# Sheet4.net
KiCad netlist of a schematic drawn in Altium Designer
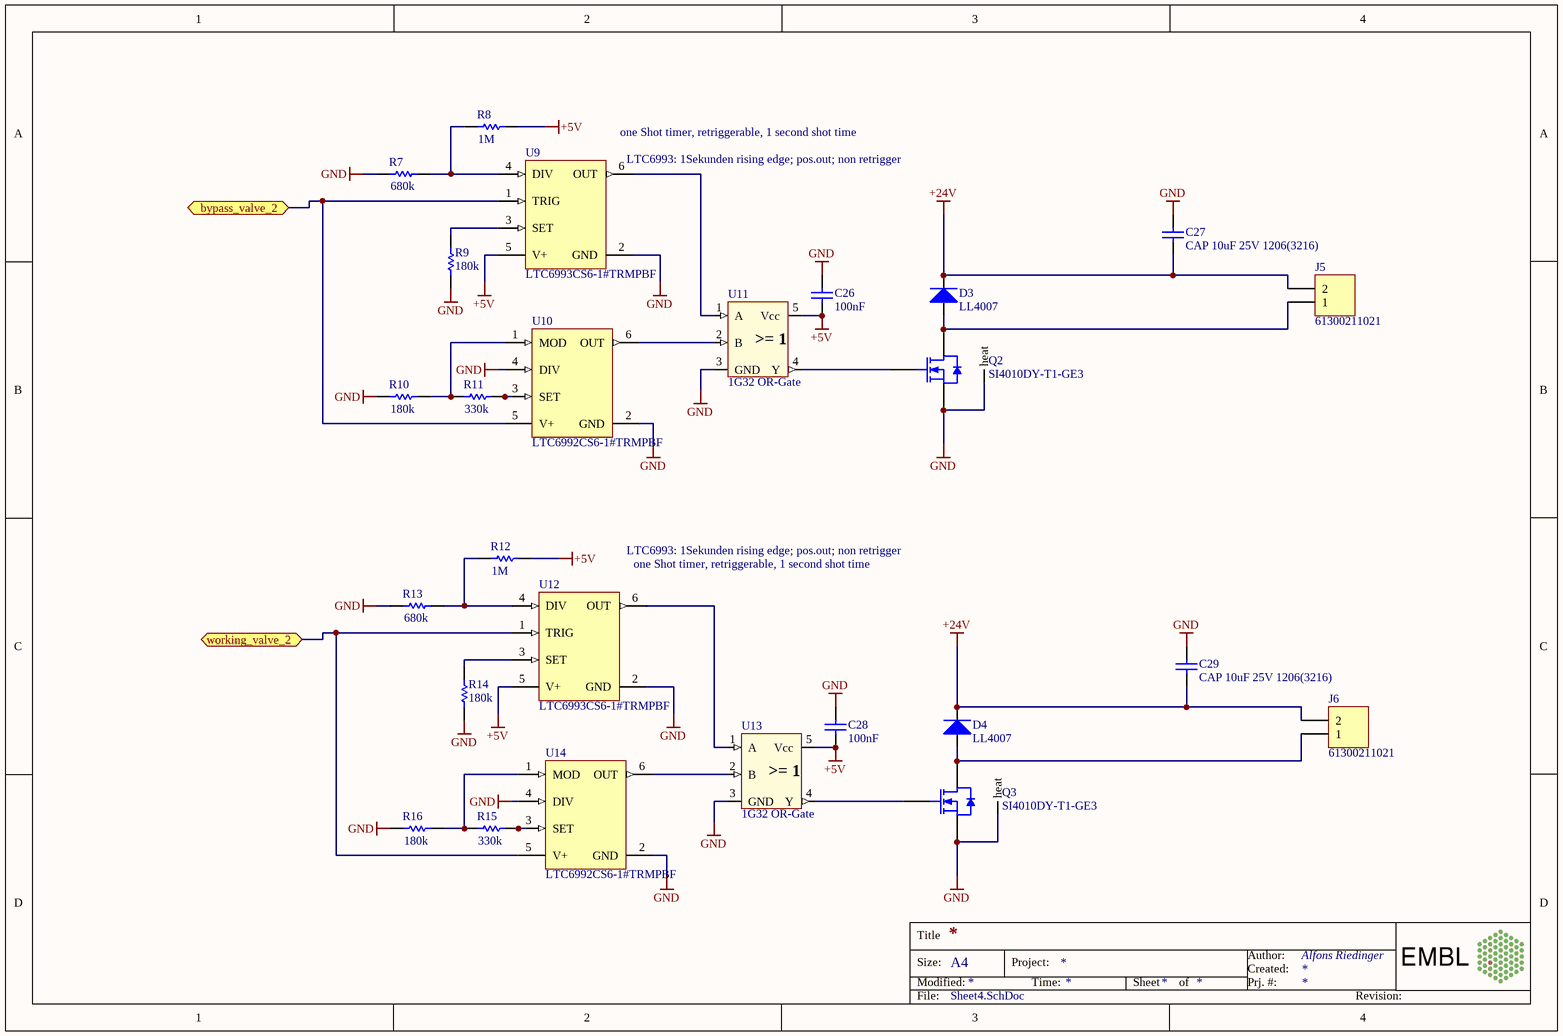
[diagram p0: Sheet4.SchDoc]

(export (version "E")
  (design (tool "Eeschema 10.0.6"))
  (components
    (comp (ref "C26")
      (value "100nF")
      (footprint "CAPC2013X88X50ML20T25")
      (description "generic 0805 COG oder X7R Vielschichtkondensatoren max. +/-10%")
      (libsource (lib "Altium Vault EMBL 3") (part "CMP-001-0082-2"))
    )
    (comp (ref "C27")
      (value "CAP 10uF 25V 1206(3216)")
      (footprint "CAPC1206(3216)190_N")
      (description "CAP 10uF 25V -20% to +80% 1206 (3216 Metric) Thickness 1.9mm SMD")
      (fields
        (field (name "TOLERANCE") "-20% to +80%")
        (field (name "MANUFACTURER") "Wurth Electronics Inc.")
      )
      (libsource (lib "Altium Vault EMBL 3") (part "CMP-00471-2"))
    )
    (comp (ref "C28")
      (value "100nF")
      (footprint "CAPC2013X88X50ML20T25")
      (description "generic 0805 COG oder X7R Vielschichtkondensatoren max. +/-10%")
      (libsource (lib "Altium Vault EMBL 3") (part "CMP-001-0082-2"))
    )
    (comp (ref "C29")
      (value "CAP 10uF 25V 1206(3216)")
      (footprint "CAPC1206(3216)190_N")
      (description "CAP 10uF 25V -20% to +80% 1206 (3216 Metric) Thickness 1.9mm SMD")
      (fields
        (field (name "TOLERANCE") "-20% to +80%")
        (field (name "MANUFACTURER") "Wurth Electronics Inc.")
      )
      (libsource (lib "Altium Vault EMBL 3") (part "CMP-00471-2"))
    )
    (comp (ref "D3")
      (value "LL4007")
      (footprint "LL4007")
      (description "LL4007;  Vf 1,1V @ 1A, If = 1A")
      (fields (field (name "MANUFACTURER") "TAIWAN SEMICONDUCTOR") (field (name "PARTNUMBER") "LL4007G L2"))
      (libsource (lib "Altium Vault EMBL 3") (part "CMP-001-0049-2"))
    )
    (comp (ref "D4")
      (value "LL4007")
      (footprint "LL4007")
      (description "LL4007;  Vf 1,1V @ 1A, If = 1A")
      (fields (field (name "MANUFACTURER") "TAIWAN SEMICONDUCTOR") (field (name "PARTNUMBER") "LL4007G L2"))
      (libsource (lib "Altium Vault EMBL 3") (part "CMP-001-0049-2"))
    )
    (comp (ref "J5")
      (value "61300211021")
      (footprint "61300211021")
      (description "2pol; WR-PHD 2.54 mm THT Angled Pin Header")
      (fields (field (name "MANUFACTURER") "Wurth Electronics"))
      (libsource (lib "Altium Vault EMBL 3") (part "CMP-001-0075-2"))
    )
    (comp (ref "J6")
      (value "61300211021")
      (footprint "61300211021")
      (description "2pol; WR-PHD 2.54 mm THT Angled Pin Header")
      (fields (field (name "MANUFACTURER") "Wurth Electronics"))
      (libsource (lib "Altium Vault EMBL 3") (part "CMP-001-0075-2"))
    )
    (comp (ref "Q2")
      (value "SI4010DY-T1-GE3")
      (footprint "PCBComponent")
      (description "N-Channel_Mosfet_30V_si4010dy; Vishay - SI4010DY-T1-GE3; 40V; Rds: 0,0034Ohm @ 10V; SOIC-8")
      (fields (field (name "MANUFACTURER") "Vishay"))
      (libsource (lib "Altium Vault EMBL 3") (part "CMP-001-0052-1"))
    )
    (comp (ref "Q3")
      (value "SI4010DY-T1-GE3")
      (footprint "PCBComponent")
      (description "N-Channel_Mosfet_30V_si4010dy; Vishay - SI4010DY-T1-GE3; 40V; Rds: 0,0034Ohm @ 10V; SOIC-8")
      (fields (field (name "MANUFACTURER") "Vishay"))
      (libsource (lib "Altium Vault EMBL 3") (part "CMP-001-0052-1"))
    )
    (comp (ref "R7")
      (value "680k")
      (footprint "YAGO-RC0805_M")
      (description "0805 Yageo Standard BlackBox Resistors")
      (fields (field (name "TOLERANCE") "±1%") (field (name "MANUFACTURER") "Yageo"))
      (libsource (lib "Altium Vault EMBL 3") (part "CMP-001-0027-2"))
    )
    (comp (ref "R8")
      (value "1M")
      (footprint "YAGO-RC0805_M")
      (description "0805 Yageo Standard BlackBox Resistors")
      (fields (field (name "TOLERANCE") "±1%") (field (name "MANUFACTURER") "Yageo"))
      (libsource (lib "Altium Vault EMBL 3") (part "CMP-001-0027-2"))
    )
    (comp (ref "R9")
      (value "180k")
      (footprint "YAGO-RC0805_M")
      (description "0805 Yageo Standard BlackBox Resistors")
      (fields (field (name "TOLERANCE") "±1%") (field (name "MANUFACTURER") "Yageo"))
      (libsource (lib "Altium Vault EMBL 3") (part "CMP-001-0027-2"))
    )
    (comp (ref "R10")
      (value "180k")
      (footprint "YAGO-RC0805_M")
      (description "0805 Yageo Standard BlackBox Resistors")
      (fields (field (name "TOLERANCE") "±1%") (field (name "MANUFACTURER") "Yageo"))
      (libsource (lib "Altium Vault EMBL 3") (part "CMP-001-0027-2"))
    )
    (comp (ref "R11")
      (value "330k")
      (footprint "YAGO-RC0805_M")
      (description "0805 Yageo Standard BlackBox Resistors")
      (fields (field (name "TOLERANCE") "±1%") (field (name "MANUFACTURER") "Yageo"))
      (libsource (lib "Altium Vault EMBL 3") (part "CMP-001-0027-2"))
    )
    (comp (ref "R12")
      (value "1M")
      (footprint "YAGO-RC0805_M")
      (description "0805 Yageo Standard BlackBox Resistors")
      (fields (field (name "TOLERANCE") "±1%") (field (name "MANUFACTURER") "Yageo"))
      (libsource (lib "Altium Vault EMBL 3") (part "CMP-001-0027-2"))
    )
    (comp (ref "R13")
      (value "680k")
      (footprint "YAGO-RC0805_M")
      (description "0805 Yageo Standard BlackBox Resistors")
      (fields (field (name "TOLERANCE") "±1%") (field (name "MANUFACTURER") "Yageo"))
      (libsource (lib "Altium Vault EMBL 3") (part "CMP-001-0027-2"))
    )
    (comp (ref "R14")
      (value "180k")
      (footprint "YAGO-RC0805_M")
      (description "0805 Yageo Standard BlackBox Resistors")
      (fields (field (name "TOLERANCE") "±1%") (field (name "MANUFACTURER") "Yageo"))
      (libsource (lib "Altium Vault EMBL 3") (part "CMP-001-0027-2"))
    )
    (comp (ref "R15")
      (value "330k")
      (footprint "YAGO-RC0805_M")
      (description "0805 Yageo Standard BlackBox Resistors")
      (fields (field (name "TOLERANCE") "±1%") (field (name "MANUFACTURER") "Yageo"))
      (libsource (lib "Altium Vault EMBL 3") (part "CMP-001-0027-2"))
    )
    (comp (ref "R16")
      (value "180k")
      (footprint "YAGO-RC0805_M")
      (description "0805 Yageo Standard BlackBox Resistors")
      (fields (field (name "TOLERANCE") "±1%") (field (name "MANUFACTURER") "Yageo"))
      (libsource (lib "Altium Vault EMBL 3") (part "CMP-001-0027-2"))
    )
    (comp (ref "U9")
      (value "LTC6993CS6-1#TRMPBF")
      (footprint "LT-S6-6-TSOT-23_L")
      (fields (field (name "MANUFACTURER") "Linear Technology"))
      (libsource (lib "Altium Vault EMBL 3") (part "CMP-00464-1"))
    )
    (comp (ref "U10")
      (value "LTC6992CS6-1#TRMPBF")
      (footprint "LT-S6-6-TSOT-23_N")
      (description "IC OSC SILICON PROG TSOT23-6")
      (fields (field (name "MANUFACTURER") "Linear Technology"))
      (libsource (lib "Altium Vault EMBL 3") (part "CMP-001-0026-A.1"))
    )
    (comp (ref "U11")
      (value "1G32 OR-Gate")
      (footprint "SOT23-5 medium density")
      (description "1G32 OR Gate; SN74AHC1G32DBVR; 2-Input positive OR Gate")
      (fields
        (field (name "MANUFACTURER") "Texas Instruments")
        (field (name "MANUFACTURER PART NUMBER") "SN74AHC1G32DBVT")
      )
      (libsource (lib "Altium Vault EMBL 3") (part "CMP-001-0059-1"))
    )
    (comp (ref "U12")
      (value "LTC6993CS6-1#TRMPBF")
      (footprint "LT-S6-6-TSOT-23_L")
      (fields (field (name "MANUFACTURER") "Linear Technology"))
      (libsource (lib "Altium Vault EMBL 3") (part "CMP-00464-1"))
    )
    (comp (ref "U13")
      (value "1G32 OR-Gate")
      (footprint "SOT23-5 medium density")
      (description "1G32 OR Gate; SN74AHC1G32DBVR; 2-Input positive OR Gate")
      (fields
        (field (name "MANUFACTURER") "Texas Instruments")
        (field (name "MANUFACTURER PART NUMBER") "SN74AHC1G32DBVT")
      )
      (libsource (lib "Altium Vault EMBL 3") (part "CMP-001-0059-1"))
    )
    (comp (ref "U14")
      (value "LTC6992CS6-1#TRMPBF")
      (footprint "LT-S6-6-TSOT-23_N")
      (description "IC OSC SILICON PROG TSOT23-6")
      (fields (field (name "MANUFACTURER") "Linear Technology"))
      (libsource (lib "Altium Vault EMBL 3") (part "CMP-001-0026-A.1"))
    )
  )
  (nets
    (net (code "1") (name "+5V") (class "Default")
      (node (ref "C26") (pin "2") (pinfunction "2_2") (pintype "passive"))
      (node (ref "C28") (pin "2") (pinfunction "2_2") (pintype "passive"))
      (node (ref "R12") (pin "2") (pinfunction "2_2") (pintype "passive"))
      (node (ref "R8") (pin "2") (pinfunction "2_2") (pintype "passive"))
      (node (ref "U11") (pin "5") (pinfunction "Vcc_5") (pintype "power_in"))
      (node (ref "U12") (pin "5") (pinfunction "V+_5") (pintype "power_in"))
      (node (ref "U13") (pin "5") (pinfunction "Vcc_5") (pintype "power_in"))
      (node (ref "U9") (pin "5") (pinfunction "V+_5") (pintype "power_in"))
    )
    (net (code "2") (name "+24V") (class "Default")
      (node (ref "C27") (pin "1") (pinfunction "1_1") (pintype "passive"))
      (node (ref "C29") (pin "1") (pinfunction "1_1") (pintype "passive"))
      (node (ref "D3") (pin "2") (pinfunction "K_2") (pintype "passive"))
      (node (ref "D4") (pin "2") (pinfunction "K_2") (pintype "passive"))
      (node (ref "J5") (pin "2") (pinfunction "2_2") (pintype "passive"))
      (node (ref "J6") (pin "2") (pinfunction "2_2") (pintype "passive"))
    )
    (net (code "3") (name "/bypass_valve_2") (class "Default")
      (node (ref "U10") (pin "5") (pinfunction "V+_5") (pintype "power_in"))
      (node (ref "U9") (pin "1") (pinfunction "TRIG_1") (pintype "input"))
    )
    (net (code "4") (name "/working_valve_2") (class "Default")
      (node (ref "U12") (pin "1") (pinfunction "TRIG_1") (pintype "input"))
      (node (ref "U14") (pin "5") (pinfunction "V+_5") (pintype "power_in"))
    )
    (net (code "5") (name "GND") (class "Default")
      (node (ref "C26") (pin "1") (pinfunction "1_1") (pintype "passive"))
      (node (ref "C27") (pin "2") (pinfunction "2_2") (pintype "passive"))
      (node (ref "C28") (pin "1") (pinfunction "1_1") (pintype "passive"))
      (node (ref "C29") (pin "2") (pinfunction "2_2") (pintype "passive"))
      (node (ref "Q2") (pin "1") (pinfunction "S_1") (pintype "passive"))
      (node (ref "Q2") (pin "2") (pinfunction "S_2") (pintype "passive"))
      (node (ref "Q2") (pin "3") (pinfunction "S_3") (pintype "passive"))
      (node (ref "Q2") (pin "9") (pinfunction "heat_9") (pintype "passive"))
      (node (ref "Q3") (pin "1") (pinfunction "S_1") (pintype "passive"))
      (node (ref "Q3") (pin "2") (pinfunction "S_2") (pintype "passive"))
      (node (ref "Q3") (pin "3") (pinfunction "S_3") (pintype "passive"))
      (node (ref "Q3") (pin "9") (pinfunction "heat_9") (pintype "passive"))
      (node (ref "R10") (pin "1") (pinfunction "1_1") (pintype "passive"))
      (node (ref "R13") (pin "1") (pinfunction "1_1") (pintype "passive"))
      (node (ref "R14") (pin "1") (pinfunction "1_1") (pintype "passive"))
      (node (ref "R16") (pin "1") (pinfunction "1_1") (pintype "passive"))
      (node (ref "R7") (pin "1") (pinfunction "1_1") (pintype "passive"))
      (node (ref "R9") (pin "1") (pinfunction "1_1") (pintype "passive"))
      (node (ref "U10") (pin "2") (pinfunction "GND_2") (pintype "power_in"))
      (node (ref "U10") (pin "4") (pinfunction "DIV_4") (pintype "input"))
      (node (ref "U11") (pin "3") (pinfunction "GND_3") (pintype "passive"))
      (node (ref "U12") (pin "2") (pinfunction "GND_2") (pintype "power_in"))
      (node (ref "U13") (pin "3") (pinfunction "GND_3") (pintype "passive"))
      (node (ref "U14") (pin "2") (pinfunction "GND_2") (pintype "power_in"))
      (node (ref "U14") (pin "4") (pinfunction "DIV_4") (pintype "input"))
      (node (ref "U9") (pin "2") (pinfunction "GND_2") (pintype "power_in"))
    )
    (net (code "6") (name "Net-(D3-A)") (class "Default")
      (node (ref "D3") (pin "1") (pinfunction "A_1") (pintype "passive"))
      (node (ref "J5") (pin "1") (pinfunction "1_1") (pintype "passive"))
      (node (ref "Q2") (pin "5") (pinfunction "D_5") (pintype "passive"))
      (node (ref "Q2") (pin "6") (pinfunction "D_6") (pintype "passive"))
      (node (ref "Q2") (pin "7") (pinfunction "D_7") (pintype "passive"))
      (node (ref "Q2") (pin "8") (pinfunction "D_8") (pintype "passive"))
    )
    (net (code "7") (name "Net-(D4-A)") (class "Default")
      (node (ref "D4") (pin "1") (pinfunction "A_1") (pintype "passive"))
      (node (ref "J6") (pin "1") (pinfunction "1_1") (pintype "passive"))
      (node (ref "Q3") (pin "5") (pinfunction "D_5") (pintype "passive"))
      (node (ref "Q3") (pin "6") (pinfunction "D_6") (pintype "passive"))
      (node (ref "Q3") (pin "7") (pinfunction "D_7") (pintype "passive"))
      (node (ref "Q3") (pin "8") (pinfunction "D_8") (pintype "passive"))
    )
    (net (code "8") (name "Net-(Q2-G)") (class "Default")
      (node (ref "Q2") (pin "4") (pinfunction "G_4") (pintype "passive"))
      (node (ref "U11") (pin "4") (pinfunction "Y_4") (pintype "output"))
    )
    (net (code "9") (name "Net-(Q3-G)") (class "Default")
      (node (ref "Q3") (pin "4") (pinfunction "G_4") (pintype "passive"))
      (node (ref "U13") (pin "4") (pinfunction "Y_4") (pintype "output"))
    )
    (net (code "10") (name "Net-(U9-DIV)") (class "Default")
      (node (ref "R7") (pin "2") (pinfunction "2_2") (pintype "passive"))
      (node (ref "R8") (pin "1") (pinfunction "1_1") (pintype "passive"))
      (node (ref "U9") (pin "4") (pinfunction "DIV_4") (pintype "input"))
    )
    (net (code "11") (name "Net-(U9-SET)") (class "Default")
      (node (ref "R9") (pin "2") (pinfunction "2_2") (pintype "passive"))
      (node (ref "U9") (pin "3") (pinfunction "SET_3") (pintype "input"))
    )
    (net (code "12") (name "Net-(U10-MOD)") (class "Default")
      (node (ref "R10") (pin "2") (pinfunction "2_2") (pintype "passive"))
      (node (ref "R11") (pin "1") (pinfunction "1_1") (pintype "passive"))
      (node (ref "U10") (pin "1") (pinfunction "MOD_1") (pintype "input"))
    )
    (net (code "13") (name "Net-(U10-OUT)") (class "Default")
      (node (ref "U10") (pin "6") (pinfunction "OUT_6") (pintype "output"))
      (node (ref "U11") (pin "2") (pinfunction "B_2") (pintype "input"))
    )
    (net (code "14") (name "Net-(U10-SET)") (class "Default")
      (node (ref "R11") (pin "2") (pinfunction "2_2") (pintype "passive"))
      (node (ref "U10") (pin "3") (pinfunction "SET_3") (pintype "input"))
    )
    (net (code "15") (name "Net-(U11-A)") (class "Default")
      (node (ref "U11") (pin "1") (pinfunction "A_1") (pintype "input"))
      (node (ref "U9") (pin "6") (pinfunction "OUT_6") (pintype "output"))
    )
    (net (code "16") (name "Net-(U12-DIV)") (class "Default")
      (node (ref "R12") (pin "1") (pinfunction "1_1") (pintype "passive"))
      (node (ref "R13") (pin "2") (pinfunction "2_2") (pintype "passive"))
      (node (ref "U12") (pin "4") (pinfunction "DIV_4") (pintype "input"))
    )
    (net (code "17") (name "Net-(U12-OUT)") (class "Default")
      (node (ref "U12") (pin "6") (pinfunction "OUT_6") (pintype "output"))
      (node (ref "U13") (pin "1") (pinfunction "A_1") (pintype "input"))
    )
    (net (code "18") (name "Net-(U12-SET)") (class "Default")
      (node (ref "R14") (pin "2") (pinfunction "2_2") (pintype "passive"))
      (node (ref "U12") (pin "3") (pinfunction "SET_3") (pintype "input"))
    )
    (net (code "19") (name "Net-(U13-B)") (class "Default")
      (node (ref "U13") (pin "2") (pinfunction "B_2") (pintype "input"))
      (node (ref "U14") (pin "6") (pinfunction "OUT_6") (pintype "output"))
    )
    (net (code "20") (name "Net-(U14-MOD)") (class "Default")
      (node (ref "R15") (pin "1") (pinfunction "1_1") (pintype "passive"))
      (node (ref "R16") (pin "2") (pinfunction "2_2") (pintype "passive"))
      (node (ref "U14") (pin "1") (pinfunction "MOD_1") (pintype "input"))
    )
    (net (code "21") (name "Net-(U14-SET)") (class "Default")
      (node (ref "R15") (pin "2") (pinfunction "2_2") (pintype "passive"))
      (node (ref "U14") (pin "3") (pinfunction "SET_3") (pintype "input"))
    )
  )
)
